# MMC_2_4_MCU.net
KiCad netlist of a schematic drawn in Altium Designer
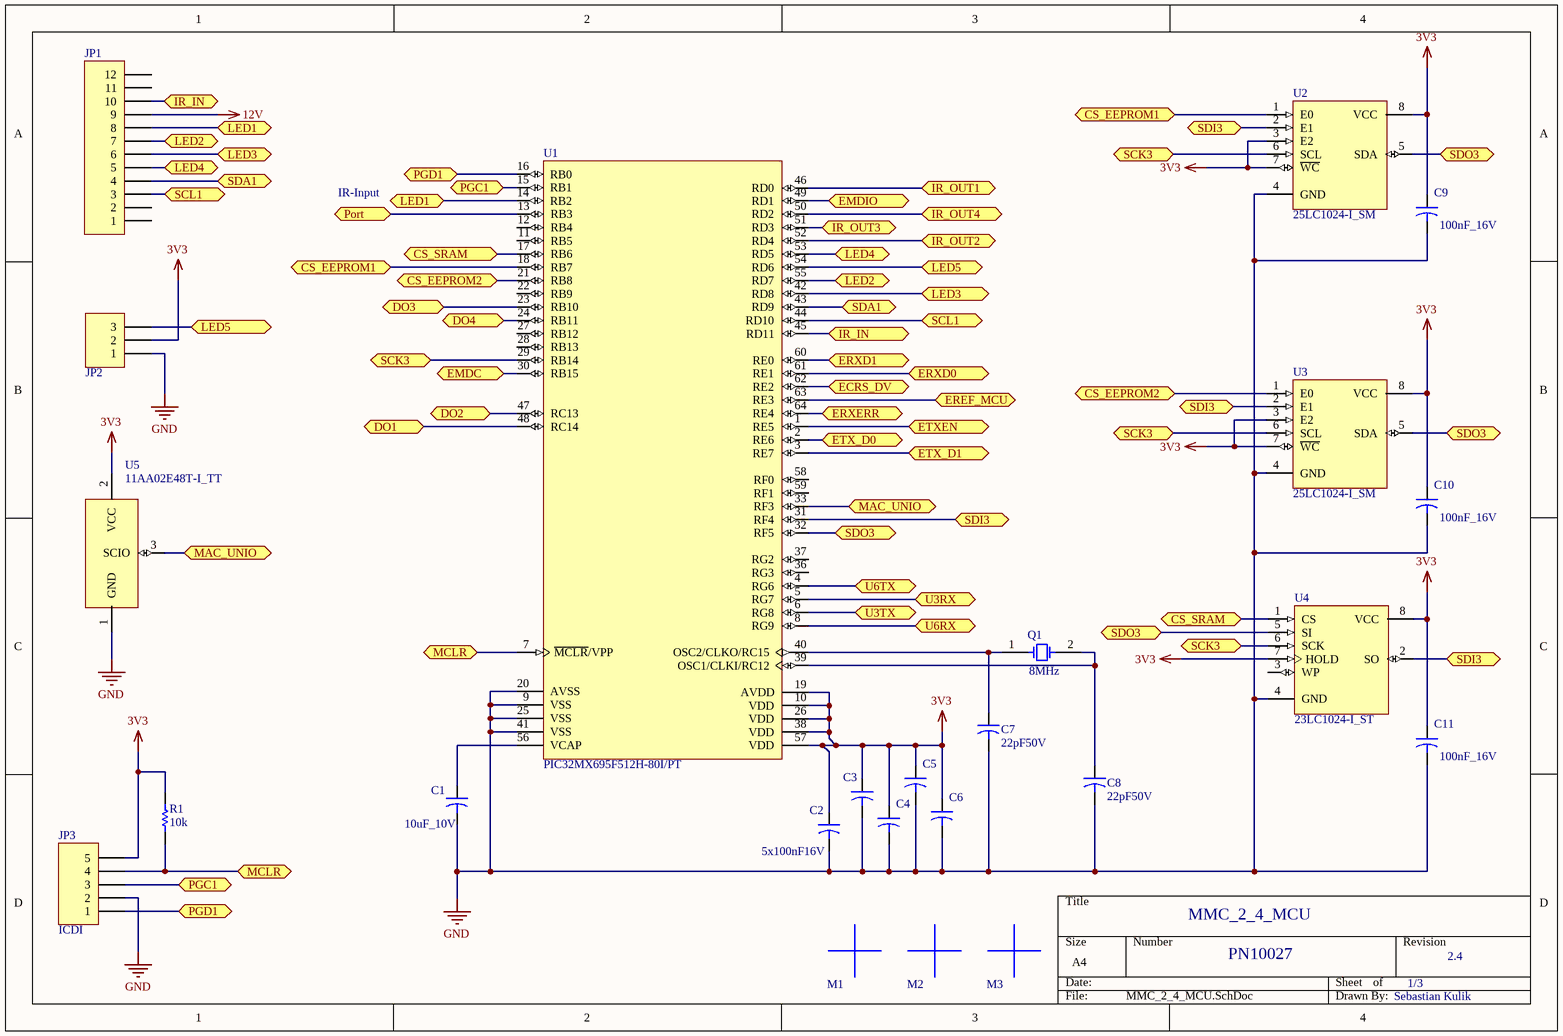
[diagram p0: MMC_2_4_MCU.SchDoc]

(export (version "E")
  (design (tool "Eeschema 10.0.6"))
  (components
    (comp (ref "C1")
      (value "10uF_10V")
      (footprint "C0603")
      (description "AVX ,  X5R, 20%, 10V")
      (fields
        (field (name "MANUFACTURER") "AVX")
        (field (name "Comment") "10uF10V_0603")
        (field (name "PUBLISHER") "Sebastian Kulik")
      )
      (libsource (lib "Capacitors") (part "10uF10V_0603"))
    )
    (comp (ref "C2")
      (value "100nF16V_0402")
      (footprint "C0402")
      (description "TDK. CGA series, X7R, 10%, 16V")
      (fields (field (name "MANUFACTURER") "TDK") (field (name "PUBLISHER") "Sebastian Kulik"))
      (libsource (lib "Capacitors") (part "100nF16V_0402"))
    )
    (comp (ref "C3")
      (value "100nF16V_0402")
      (footprint "C0402")
      (description "TDK. CGA series, X7R, 10%, 16V")
      (fields (field (name "MANUFACTURER") "TDK") (field (name "PUBLISHER") "Sebastian Kulik"))
      (libsource (lib "Capacitors") (part "100nF16V_0402"))
    )
    (comp (ref "C4")
      (value "100nF16V_0402")
      (footprint "C0402")
      (description "TDK. CGA series, X7R, 10%, 16V")
      (fields (field (name "MANUFACTURER") "TDK") (field (name "PUBLISHER") "Sebastian Kulik"))
      (libsource (lib "Capacitors") (part "100nF16V_0402"))
    )
    (comp (ref "C5")
      (value "100nF16V_0402")
      (footprint "C0402")
      (description "TDK. CGA series, X7R, 10%, 16V")
      (fields (field (name "MANUFACTURER") "TDK") (field (name "PUBLISHER") "Sebastian Kulik"))
      (libsource (lib "Capacitors") (part "100nF16V_0402"))
    )
    (comp (ref "C6")
      (value "100nF16V_0402")
      (footprint "C0402")
      (description "TDK. CGA series, X7R, 10%, 16V")
      (fields (field (name "MANUFACTURER") "TDK") (field (name "PUBLISHER") "Sebastian Kulik"))
      (libsource (lib "Capacitors") (part "100nF16V_0402"))
    )
    (comp (ref "C7")
      (value "22pF50V")
      (footprint "C0402")
      (description "AVX, 50V")
      (fields
        (field (name "MANUFACTURER") "AVX")
        (field (name "Comment") "22pF50V_0402-AVX")
        (field (name "PUBLISHER") "Sebastian Kulik")
      )
      (libsource (lib "Capacitors") (part "22pF50V_0402-AVX"))
    )
    (comp (ref "C8")
      (value "22pF50V")
      (footprint "C0402")
      (description "AVX, 50V")
      (fields
        (field (name "MANUFACTURER") "AVX")
        (field (name "Comment") "22pF50V_0402-AVX")
        (field (name "PUBLISHER") "Sebastian Kulik")
      )
      (libsource (lib "Capacitors") (part "22pF50V_0402-AVX"))
    )
    (comp (ref "C9")
      (value "100nF_16V")
      (footprint "C0402")
      (description "TDK. CGA series, X7R, 10%, 16V")
      (fields
        (field (name "MANUFACTURER") "TDK")
        (field (name "Comment") "100nF16V_0402")
        (field (name "PUBLISHER") "Sebastian Kulik")
      )
      (libsource (lib "Capacitors") (part "100nF16V_0402"))
    )
    (comp (ref "C10")
      (value "100nF_16V")
      (footprint "C0402")
      (description "TDK. CGA series, X7R, 10%, 16V")
      (fields
        (field (name "MANUFACTURER") "TDK")
        (field (name "Comment") "100nF16V_0402")
        (field (name "PUBLISHER") "Sebastian Kulik")
      )
      (libsource (lib "Capacitors") (part "100nF16V_0402"))
    )
    (comp (ref "C11")
      (value "100nF_16V")
      (footprint "C0402")
      (description "TDK. CGA series, X7R, 10%, 16V")
      (fields
        (field (name "MANUFACTURER") "TDK")
        (field (name "Comment") "100nF16V_0402")
        (field (name "PUBLISHER") "Sebastian Kulik")
      )
      (libsource (lib "Capacitors") (part "100nF16V_0402"))
    )
    (comp (ref "JP1")
      (value "Plug_12_2.54")
      (footprint "HDR1X12_2.54")
      (description "Plug, 11-Pin")
      (fields (field (name "MANUFACTURER") "WE") (field (name "PUBLISHER") "Sebastian Kulik"))
      (libsource (lib "Connectors") (part "Plug_12_2.54"))
    )
    (comp (ref "JP2")
      (value "Header-3")
      (footprint "HDR1X3")
      (description "Header-3-Pin")
      (fields (field (name "PUBLISHER") "Sebastian Kulik"))
      (libsource (lib "Connectors") (part "Header-3"))
    )
    (comp (ref "JP3")
      (value "ICDI")
      (footprint "HDR1X5-1.27")
      (description "Header, 5-Pin")
      (fields (field (name "PUBLISHER") "Sebastian Kulik"))
      (libsource (lib "Connectors") (part "ICDI"))
    )
    (comp (ref "M1") (value "Paste Mark") (footprint "Mark-3mm") (libsource (lib "Symbols") (part "Mark")))
    (comp (ref "M2") (value "Paste Mark") (footprint "Mark-3mm") (libsource (lib "Symbols") (part "Mark")))
    (comp (ref "M3") (value "Paste Mark") (footprint "Mark-3mm") (libsource (lib "Symbols") (part "Mark")))
    (comp (ref "Q1")
      (value "8MHz")
      (footprint "TXC_7A")
      (description "Crystal, 7A-8.000MAAJ-T")
      (fields
        (field (name "MANUFACTURER") "TXC")
        (field (name "Comment") "Crystal_8MHz")
        (field (name "PUBLISHER") "Sebastian Kulik")
      )
      (libsource (lib "Passives") (part "Crystal_8MHz"))
    )
    (comp (ref "R1")
      (value "10k")
      (footprint "R0402")
      (description "Vishay CRCW series, 125mW, 1%")
      (fields
        (field (name "MANUFACTURER") "Vishay")
        (field (name "Comment") "10k_0402")
        (field (name "PUBLISHER") "Sebastian Kulik")
      )
      (libsource (lib "Resistors") (part "10k_0402"))
    )
    (comp (ref "U1")
      (value "PIC32MX695F512H-80I/PT")
      (footprint "TQFP-64_N1")
      (fields (field (name "MANUFACTURER") "Microchip") (field (name "PUBLISHER") "Sebastian Kulik"))
      (libsource (lib "ICs") (part "PIC32MX695F512H-80I/PT"))
    )
    (comp (ref "U2")
      (value "25LC1024-I_SM")
      (footprint "SOP8_N")
      (description "1024 Kbit Serial SPI Bus EEPROM")
      (fields (field (name "MANUFACTURER") "Microchip") (field (name "PUBLISHER") "Sebastian Kulik"))
      (libsource (lib "ICs") (part "25LC1024-I_SM"))
    )
    (comp (ref "U3")
      (value "25LC1024-I_SM")
      (footprint "SOP8_N")
      (description "1024 Kbit Serial SPI Bus EEPROM")
      (fields (field (name "MANUFACTURER") "Microchip") (field (name "PUBLISHER") "Sebastian Kulik"))
      (libsource (lib "ICs") (part "25LC1024-I_SM"))
    )
    (comp (ref "U4")
      (value "23LC1024-I_ST")
      (footprint "TSSOP8")
      (description "1 Mbit Serial  EEPROM")
      (fields (field (name "MANUFACTURER") "Microchip") (field (name "PUBLISHER") "Sebastian Kulik"))
      (libsource (lib "ICs") (part "23LC1024-I_ST"))
    )
    (comp (ref "U5")
      (value "11AA02E48T-I_TT")
      (footprint "SOT23_M")
      (description "2 kbit Serial  EEPROM")
      (fields (field (name "MANUFACTURER") "Microchip") (field (name "PUBLISHER") "Sebastian Kulik"))
      (libsource (lib "ICs") (part "11AA02E48T-I_TT"))
    )
  )
  (nets
    (net (code "1") (name "/CS_EEPROM1") (class "Default")
      (node (ref "U1") (pin "18") (pinfunction "RB7_18") (pintype "bidirectional"))
      (node (ref "U2") (pin "1") (pinfunction "E0_1") (pintype "input"))
    )
    (net (code "2") (name "/CS_EEPROM2") (class "Default")
      (node (ref "U1") (pin "21") (pinfunction "RB8_21") (pintype "bidirectional"))
      (node (ref "U3") (pin "1") (pinfunction "E0_1") (pintype "input"))
    )
    (net (code "3") (name "/CS_SRAM") (class "Default")
      (node (ref "U1") (pin "17") (pinfunction "RB6_17") (pintype "bidirectional"))
      (node (ref "U4") (pin "1") (pinfunction "CS_1") (pintype "input"))
    )
    (net (code "4") (name "/DO1") (class "Default")
      (node (ref "U1") (pin "48") (pinfunction "RC14_48") (pintype "bidirectional"))
    )
    (net (code "5") (name "/DO2") (class "Default")
      (node (ref "U1") (pin "47") (pinfunction "RC13_47") (pintype "bidirectional"))
    )
    (net (code "6") (name "/DO3") (class "Default")
      (node (ref "U1") (pin "23") (pinfunction "RB10_23") (pintype "bidirectional"))
    )
    (net (code "7") (name "/DO4") (class "Default")
      (node (ref "U1") (pin "24") (pinfunction "RB11_24") (pintype "bidirectional"))
    )
    (net (code "8") (name "/ECRS_DV") (class "Default")
      (node (ref "U1") (pin "62") (pinfunction "RE2_62") (pintype "bidirectional"))
    )
    (net (code "9") (name "/EMDC") (class "Default")
      (node (ref "U1") (pin "30") (pinfunction "RB15_30") (pintype "bidirectional"))
    )
    (net (code "10") (name "/EMDIO") (class "Default")
      (node (ref "U1") (pin "49") (pinfunction "RD1_49") (pintype "bidirectional"))
    )
    (net (code "11") (name "/EREF_MCU") (class "Default")
      (node (ref "U1") (pin "63") (pinfunction "RE3_63") (pintype "bidirectional"))
    )
    (net (code "12") (name "/ERXD0") (class "Default")
      (node (ref "U1") (pin "61") (pinfunction "RE1_61") (pintype "bidirectional"))
    )
    (net (code "13") (name "/ERXD1") (class "Default")
      (node (ref "U1") (pin "60") (pinfunction "RE0_60") (pintype "bidirectional"))
    )
    (net (code "14") (name "/ERXERR") (class "Default")
      (node (ref "U1") (pin "64") (pinfunction "RE4_64") (pintype "bidirectional"))
    )
    (net (code "15") (name "/ETXEN") (class "Default")
      (node (ref "U1") (pin "1") (pinfunction "RE5_1") (pintype "bidirectional"))
    )
    (net (code "16") (name "/ETX_D0") (class "Default")
      (node (ref "U1") (pin "2") (pinfunction "RE6_2") (pintype "bidirectional"))
    )
    (net (code "17") (name "/ETX_D1") (class "Default")
      (node (ref "U1") (pin "3") (pinfunction "RE7_3") (pintype "bidirectional"))
    )
    (net (code "18") (name "/IR_IN") (class "Default")
      (node (ref "JP1") (pin "10") (pinfunction "10_10") (pintype "passive"))
      (node (ref "U1") (pin "45") (pinfunction "RD11_45") (pintype "bidirectional"))
    )
    (net (code "19") (name "/IR_OUT1") (class "Default")
      (node (ref "U1") (pin "46") (pinfunction "RD0_46") (pintype "bidirectional"))
    )
    (net (code "20") (name "/IR_OUT2") (class "Default")
      (node (ref "U1") (pin "52") (pinfunction "RD4_52") (pintype "bidirectional"))
    )
    (net (code "21") (name "/IR_OUT3") (class "Default")
      (node (ref "U1") (pin "51") (pinfunction "RD3_51") (pintype "bidirectional"))
    )
    (net (code "22") (name "/IR_OUT4") (class "Default")
      (node (ref "U1") (pin "50") (pinfunction "RD2_50") (pintype "bidirectional"))
    )
    (net (code "23") (name "/LED1") (class "Default")
      (node (ref "JP1") (pin "8") (pinfunction "8_8") (pintype "passive"))
      (node (ref "U1") (pin "14") (pinfunction "RB2_14") (pintype "bidirectional"))
    )
    (net (code "24") (name "/LED2") (class "Default")
      (node (ref "JP1") (pin "7") (pinfunction "7_7") (pintype "passive"))
      (node (ref "U1") (pin "55") (pinfunction "RD7_55") (pintype "bidirectional"))
    )
    (net (code "25") (name "/LED3") (class "Default")
      (node (ref "JP1") (pin "6") (pinfunction "6_6") (pintype "passive"))
      (node (ref "U1") (pin "42") (pinfunction "RD8_42") (pintype "bidirectional"))
    )
    (net (code "26") (name "/LED4") (class "Default")
      (node (ref "JP1") (pin "5") (pinfunction "5_5") (pintype "passive"))
      (node (ref "U1") (pin "53") (pinfunction "RD5_53") (pintype "bidirectional"))
    )
    (net (code "27") (name "/LED5") (class "Default")
      (node (ref "JP2") (pin "3") (pinfunction "3_3") (pintype "passive"))
      (node (ref "U1") (pin "54") (pinfunction "RD6_54") (pintype "bidirectional"))
    )
    (net (code "28") (name "/MAC_UNIO") (class "Default")
      (node (ref "U1") (pin "33") (pinfunction "RF3_33") (pintype "bidirectional"))
      (node (ref "U5") (pin "3") (pinfunction "SCIO_3") (pintype "bidirectional"))
    )
    (net (code "29") (name "/MCLR") (class "Default")
      (node (ref "JP3") (pin "4") (pinfunction "4_4") (pintype "passive"))
      (node (ref "R1") (pin "1") (pinfunction "1_1") (pintype "passive"))
      (node (ref "U1") (pin "7") (pinfunction "~{MCLR}/VPP_7") (pintype "input"))
    )
    (net (code "30") (name "/PGC1") (class "Default")
      (node (ref "JP3") (pin "3") (pinfunction "3_3") (pintype "passive"))
      (node (ref "U1") (pin "15") (pinfunction "RB1_15") (pintype "bidirectional"))
    )
    (net (code "31") (name "/PGD1") (class "Default")
      (node (ref "JP3") (pin "1") (pinfunction "1_1") (pintype "passive"))
      (node (ref "U1") (pin "16") (pinfunction "RB0_16") (pintype "bidirectional"))
    )
    (net (code "32") (name "/Port") (class "Default")
      (node (ref "U1") (pin "13") (pinfunction "RB3_13") (pintype "bidirectional"))
    )
    (net (code "33") (name "/SCK3") (class "Default")
      (node (ref "U1") (pin "29") (pinfunction "RB14_29") (pintype "bidirectional"))
      (node (ref "U2") (pin "6") (pinfunction "SCL_6") (pintype "input"))
      (node (ref "U3") (pin "6") (pinfunction "SCL_6") (pintype "input"))
      (node (ref "U4") (pin "6") (pinfunction "SCK_6") (pintype "input"))
    )
    (net (code "34") (name "/SCL1") (class "Default")
      (node (ref "JP1") (pin "3") (pinfunction "3_3") (pintype "passive"))
      (node (ref "U1") (pin "44") (pinfunction "RD10_44") (pintype "bidirectional"))
    )
    (net (code "35") (name "/SDA1") (class "Default")
      (node (ref "JP1") (pin "4") (pinfunction "4_4") (pintype "passive"))
      (node (ref "U1") (pin "43") (pinfunction "RD9_43") (pintype "bidirectional"))
    )
    (net (code "36") (name "/SDI3") (class "Default")
      (node (ref "U1") (pin "31") (pinfunction "RF4_31") (pintype "bidirectional"))
      (node (ref "U2") (pin "2") (pinfunction "E1_2") (pintype "input"))
      (node (ref "U3") (pin "2") (pinfunction "E1_2") (pintype "input"))
      (node (ref "U4") (pin "2") (pinfunction "SO_2") (pintype "bidirectional"))
    )
    (net (code "37") (name "/SDO3") (class "Default")
      (node (ref "U1") (pin "32") (pinfunction "RF5_32") (pintype "bidirectional"))
      (node (ref "U2") (pin "5") (pinfunction "SDA_5") (pintype "bidirectional"))
      (node (ref "U3") (pin "5") (pinfunction "SDA_5") (pintype "bidirectional"))
      (node (ref "U4") (pin "5") (pinfunction "SI_5") (pintype "input"))
    )
    (net (code "38") (name "/U3RX") (class "Default")
      (node (ref "U1") (pin "5") (pinfunction "RG7_5") (pintype "bidirectional"))
    )
    (net (code "39") (name "/U3TX") (class "Default")
      (node (ref "U1") (pin "6") (pinfunction "RG8_6") (pintype "bidirectional"))
    )
    (net (code "40") (name "/U6RX") (class "Default")
      (node (ref "U1") (pin "8") (pinfunction "RG9_8") (pintype "bidirectional"))
    )
    (net (code "41") (name "/U6TX") (class "Default")
      (node (ref "U1") (pin "4") (pinfunction "RG6_4") (pintype "bidirectional"))
    )
    (net (code "42") (name "3V3") (class "Default")
      (node (ref "C10") (pin "1") (pinfunction "1_1") (pintype "passive"))
      (node (ref "C11") (pin "1") (pinfunction "1_1") (pintype "passive"))
      (node (ref "C2") (pin "1") (pinfunction "1_1") (pintype "passive"))
      (node (ref "C3") (pin "1") (pinfunction "1_1") (pintype "passive"))
      (node (ref "C4") (pin "1") (pinfunction "1_1") (pintype "passive"))
      (node (ref "C5") (pin "1") (pinfunction "1_1") (pintype "passive"))
      (node (ref "C6") (pin "1") (pinfunction "1_1") (pintype "passive"))
      (node (ref "C9") (pin "1") (pinfunction "1_1") (pintype "passive"))
      (node (ref "JP2") (pin "2") (pinfunction "2_2") (pintype "passive"))
      (node (ref "JP3") (pin "5") (pinfunction "5_5") (pintype "passive"))
      (node (ref "R1") (pin "2") (pinfunction "2_2") (pintype "passive"))
      (node (ref "U1") (pin "10") (pinfunction "VDD_10") (pintype "power_in"))
      (node (ref "U1") (pin "19") (pinfunction "AVDD_19") (pintype "power_in"))
      (node (ref "U1") (pin "26") (pinfunction "VDD_26") (pintype "power_in"))
      (node (ref "U1") (pin "38") (pinfunction "VDD_38") (pintype "power_in"))
      (node (ref "U1") (pin "57") (pinfunction "VDD_57") (pintype "power_in"))
      (node (ref "U2") (pin "3") (pinfunction "E2_3") (pintype "input"))
      (node (ref "U2") (pin "7") (pinfunction "~{WC}_7") (pintype "bidirectional"))
      (node (ref "U2") (pin "8") (pinfunction "VCC_8") (pintype "power_in"))
      (node (ref "U3") (pin "3") (pinfunction "E2_3") (pintype "input"))
      (node (ref "U3") (pin "7") (pinfunction "~{WC}_7") (pintype "bidirectional"))
      (node (ref "U3") (pin "8") (pinfunction "VCC_8") (pintype "power_in"))
      (node (ref "U4") (pin "7") (pinfunction "HOLD_7") (pintype "input"))
      (node (ref "U4") (pin "8") (pinfunction "VCC_8") (pintype "power_in"))
      (node (ref "U5") (pin "2") (pinfunction "VCC_2") (pintype "power_in"))
    )
    (net (code "43") (name "12V") (class "Default")
      (node (ref "JP1") (pin "9") (pinfunction "9_9") (pintype "passive"))
    )
    (net (code "44") (name "GND") (class "Default")
      (node (ref "C1") (pin "2") (pinfunction "2_2") (pintype "passive"))
      (node (ref "C10") (pin "2") (pinfunction "2_2") (pintype "passive"))
      (node (ref "C11") (pin "2") (pinfunction "2_2") (pintype "passive"))
      (node (ref "C2") (pin "2") (pinfunction "2_2") (pintype "passive"))
      (node (ref "C3") (pin "2") (pinfunction "2_2") (pintype "passive"))
      (node (ref "C4") (pin "2") (pinfunction "2_2") (pintype "passive"))
      (node (ref "C5") (pin "2") (pinfunction "2_2") (pintype "passive"))
      (node (ref "C6") (pin "2") (pinfunction "2_2") (pintype "passive"))
      (node (ref "C7") (pin "2") (pinfunction "2_2") (pintype "passive"))
      (node (ref "C8") (pin "2") (pinfunction "2_2") (pintype "passive"))
      (node (ref "C9") (pin "2") (pinfunction "2_2") (pintype "passive"))
      (node (ref "JP2") (pin "1") (pinfunction "1_1") (pintype "passive"))
      (node (ref "JP3") (pin "2") (pinfunction "2_2") (pintype "passive"))
      (node (ref "U1") (pin "20") (pinfunction "AVSS_20") (pintype "power_in"))
      (node (ref "U1") (pin "25") (pinfunction "VSS_25") (pintype "power_in"))
      (node (ref "U1") (pin "41") (pinfunction "VSS_41") (pintype "power_in"))
      (node (ref "U1") (pin "9") (pinfunction "VSS_9") (pintype "power_in"))
      (node (ref "U2") (pin "4") (pinfunction "GND_4") (pintype "power_in"))
      (node (ref "U3") (pin "4") (pinfunction "GND_4") (pintype "power_in"))
      (node (ref "U4") (pin "4") (pinfunction "GND_4") (pintype "power_in"))
      (node (ref "U5") (pin "1") (pinfunction "GND_1") (pintype "power_in"))
    )
    (net (code "45") (name "Net-(U1-OSC1{slash}CLKI{slash}RC12)") (class "Default")
      (node (ref "C8") (pin "1") (pinfunction "1_1") (pintype "passive"))
      (node (ref "Q1") (pin "2") (pinfunction "2_2") (pintype "passive"))
      (node (ref "U1") (pin "39") (pinfunction "OSC1/CLKI/RC12_39") (pintype "bidirectional"))
    )
    (net (code "46") (name "Net-(U1-OSC2{slash}CLKO{slash}RC15)") (class "Default")
      (node (ref "C7") (pin "1") (pinfunction "1_1") (pintype "passive"))
      (node (ref "Q1") (pin "1") (pinfunction "1_1") (pintype "passive"))
      (node (ref "U1") (pin "40") (pinfunction "OSC2/CLKO/RC15_40") (pintype "output"))
    )
    (net (code "47") (name "Net-(U1-VCAP)") (class "Default")
      (node (ref "C1") (pin "1") (pinfunction "1_1") (pintype "passive"))
      (node (ref "U1") (pin "56") (pinfunction "VCAP_56") (pintype "power_in"))
    )
    (net (code "48") (name "unconnected-(JP1-Pad1)") (class "Default")
      (node (ref "JP1") (pin "1") (pinfunction "1_1") (pintype "passive"))
    )
    (net (code "49") (name "unconnected-(JP1-Pad2)") (class "Default")
      (node (ref "JP1") (pin "2") (pinfunction "2_2") (pintype "passive"))
    )
    (net (code "50") (name "unconnected-(JP1-Pad11)") (class "Default")
      (node (ref "JP1") (pin "11") (pinfunction "11_11") (pintype "passive"))
    )
    (net (code "51") (name "unconnected-(JP1-Pad12)") (class "Default")
      (node (ref "JP1") (pin "12") (pinfunction "12_12") (pintype "passive"))
    )
    (net (code "52") (name "unconnected-(U1-RB4-Pad12)") (class "Default")
      (node (ref "U1") (pin "12") (pinfunction "RB4_12") (pintype "bidirectional"))
    )
    (net (code "53") (name "unconnected-(U1-RB5-Pad11)") (class "Default")
      (node (ref "U1") (pin "11") (pinfunction "RB5_11") (pintype "bidirectional"))
    )
    (net (code "54") (name "unconnected-(U1-RB9-Pad22)") (class "Default")
      (node (ref "U1") (pin "22") (pinfunction "RB9_22") (pintype "bidirectional"))
    )
    (net (code "55") (name "unconnected-(U1-RB12-Pad27)") (class "Default")
      (node (ref "U1") (pin "27") (pinfunction "RB12_27") (pintype "bidirectional"))
    )
    (net (code "56") (name "unconnected-(U1-RB13-Pad28)") (class "Default")
      (node (ref "U1") (pin "28") (pinfunction "RB13_28") (pintype "bidirectional"))
    )
    (net (code "57") (name "unconnected-(U1-RF0-Pad58)") (class "Default")
      (node (ref "U1") (pin "58") (pinfunction "RF0_58") (pintype "bidirectional"))
    )
    (net (code "58") (name "unconnected-(U1-RF1-Pad59)") (class "Default")
      (node (ref "U1") (pin "59") (pinfunction "RF1_59") (pintype "bidirectional"))
    )
    (net (code "59") (name "unconnected-(U1-RG2-Pad37)") (class "Default")
      (node (ref "U1") (pin "37") (pinfunction "RG2_37") (pintype "bidirectional"))
    )
    (net (code "60") (name "unconnected-(U1-RG3-Pad36)") (class "Default")
      (node (ref "U1") (pin "36") (pinfunction "RG3_36") (pintype "bidirectional"))
    )
    (net (code "61") (name "unconnected-(U4-WP-Pad3)") (class "Default")
      (node (ref "U4") (pin "3") (pinfunction "WP_3") (pintype "bidirectional"))
    )
  )
)
